# controls_rev_2.net
KiCad netlist of a schematic drawn in EAGLE
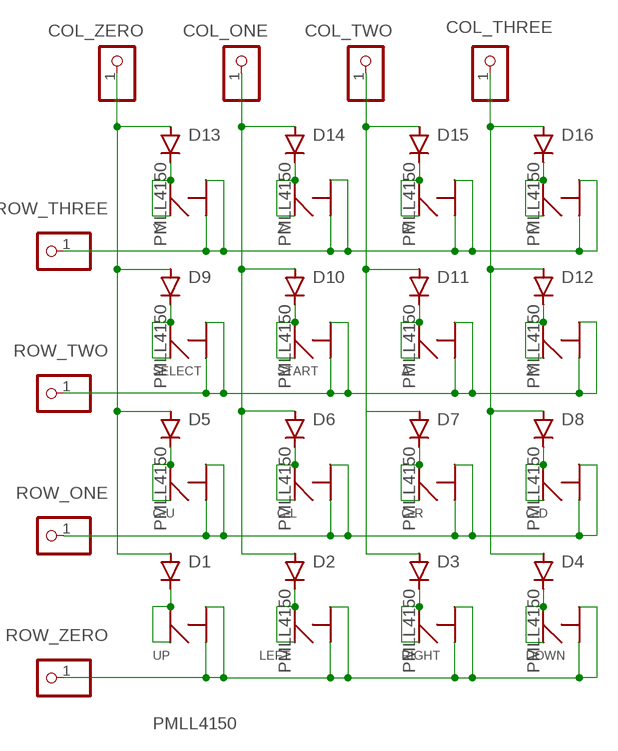
[diagram p0: schematic, sheet 1]

(export (version "E")
  (design (tool "Eeschema 10.0.6"))
  (components
    (comp (ref "A")
      (value "EVQQ2")
      (footprint "eagle-import:TACT")
      (libsource (lib "eagle-import") (part "EVQQ2"))
    )
    (comp (ref "B")
      (value "EVQQ2")
      (footprint "eagle-import:TACT")
      (libsource (lib "eagle-import") (part "EVQQ2"))
    )
    (comp (ref "C")
      (value "EVQQ2")
      (footprint "eagle-import:TACT")
      (libsource (lib "eagle-import") (part "EVQQ2"))
    )
    (comp (ref "C-D")
      (value "EVQQ2")
      (footprint "eagle-import:TACT")
      (libsource (lib "eagle-import") (part "EVQQ2"))
    )
    (comp (ref "C-L")
      (value "EVQQ2")
      (footprint "eagle-import:TACT")
      (libsource (lib "eagle-import") (part "EVQQ2"))
    )
    (comp (ref "C-R")
      (value "EVQQ2")
      (footprint "eagle-import:TACT")
      (libsource (lib "eagle-import") (part "EVQQ2"))
    )
    (comp (ref "C-U")
      (value "EVQQ2")
      (footprint "eagle-import:TACT")
      (libsource (lib "eagle-import") (part "EVQQ2"))
    )
    (comp (ref "COL_ONE")
      (value "PINHD-1X1")
      (footprint "eagle-import:1X01")
      (libsource (lib "eagle-import") (part "PINHD-1X1"))
    )
    (comp (ref "COL_THREE")
      (value "PINHD-1X1")
      (footprint "eagle-import:1X01")
      (libsource (lib "eagle-import") (part "PINHD-1X1"))
    )
    (comp (ref "COL_TWO")
      (value "PINHD-1X1")
      (footprint "eagle-import:1X01")
      (libsource (lib "eagle-import") (part "PINHD-1X1"))
    )
    (comp (ref "COL_ZERO")
      (value "PINHD-1X1")
      (footprint "eagle-import:1X01")
      (libsource (lib "eagle-import") (part "PINHD-1X1"))
    )
    (comp (ref "D1")
      (value "PMLL4150")
      (footprint "eagle-import:SOD80C")
      (libsource (lib "eagle-import") (part "PMLL4150"))
    )
    (comp (ref "D2")
      (value "PMLL4150")
      (footprint "eagle-import:SOD80C")
      (libsource (lib "eagle-import") (part "PMLL4150"))
    )
    (comp (ref "D3")
      (value "PMLL4150")
      (footprint "eagle-import:SOD80C")
      (libsource (lib "eagle-import") (part "PMLL4150"))
    )
    (comp (ref "D4")
      (value "PMLL4150")
      (footprint "eagle-import:SOD80C")
      (libsource (lib "eagle-import") (part "PMLL4150"))
    )
    (comp (ref "D5")
      (value "PMLL4150")
      (footprint "eagle-import:SOD80C")
      (libsource (lib "eagle-import") (part "PMLL4150"))
    )
    (comp (ref "D6")
      (value "PMLL4150")
      (footprint "eagle-import:SOD80C")
      (libsource (lib "eagle-import") (part "PMLL4150"))
    )
    (comp (ref "D7")
      (value "PMLL4150")
      (footprint "eagle-import:SOD80C")
      (libsource (lib "eagle-import") (part "PMLL4150"))
    )
    (comp (ref "D8")
      (value "PMLL4150")
      (footprint "eagle-import:SOD80C")
      (libsource (lib "eagle-import") (part "PMLL4150"))
    )
    (comp (ref "D9")
      (value "PMLL4150")
      (footprint "eagle-import:SOD80C")
      (libsource (lib "eagle-import") (part "PMLL4150"))
    )
    (comp (ref "D10")
      (value "PMLL4150")
      (footprint "eagle-import:SOD80C")
      (libsource (lib "eagle-import") (part "PMLL4150"))
    )
    (comp (ref "D11")
      (value "PMLL4150")
      (footprint "eagle-import:SOD80C")
      (libsource (lib "eagle-import") (part "PMLL4150"))
    )
    (comp (ref "D12")
      (value "PMLL4150")
      (footprint "eagle-import:SOD80C")
      (libsource (lib "eagle-import") (part "PMLL4150"))
    )
    (comp (ref "D13")
      (value "PMLL4150")
      (footprint "eagle-import:SOD80C")
      (libsource (lib "eagle-import") (part "PMLL4150"))
    )
    (comp (ref "D14")
      (value "PMLL4150")
      (footprint "eagle-import:SOD80C")
      (libsource (lib "eagle-import") (part "PMLL4150"))
    )
    (comp (ref "D15")
      (value "PMLL4150")
      (footprint "eagle-import:SOD80C")
      (libsource (lib "eagle-import") (part "PMLL4150"))
    )
    (comp (ref "D16")
      (value "PMLL4150")
      (footprint "eagle-import:SOD80C")
      (libsource (lib "eagle-import") (part "PMLL4150"))
    )
    (comp (ref "DOWN")
      (value "EVQQ2")
      (footprint "eagle-import:TACT")
      (libsource (lib "eagle-import") (part "EVQQ2"))
    )
    (comp (ref "LEFT")
      (value "EVQQ2")
      (footprint "eagle-import:TACT")
      (libsource (lib "eagle-import") (part "EVQQ2"))
    )
    (comp (ref "RIGHT")
      (value "EVQQ2")
      (footprint "eagle-import:TACT")
      (libsource (lib "eagle-import") (part "EVQQ2"))
    )
    (comp (ref "ROW_ONE")
      (value "PINHD-1X1")
      (footprint "eagle-import:1X01")
      (libsource (lib "eagle-import") (part "PINHD-1X1"))
    )
    (comp (ref "ROW_THREE")
      (value "PINHD-1X1")
      (footprint "eagle-import:1X01")
      (libsource (lib "eagle-import") (part "PINHD-1X1"))
    )
    (comp (ref "ROW_TWO")
      (value "PINHD-1X1")
      (footprint "eagle-import:1X01")
      (libsource (lib "eagle-import") (part "PINHD-1X1"))
    )
    (comp (ref "ROW_ZERO")
      (value "PINHD-1X1")
      (footprint "eagle-import:1X01")
      (libsource (lib "eagle-import") (part "PINHD-1X1"))
    )
    (comp (ref "SELECT")
      (value "EVQQ2")
      (footprint "eagle-import:TACT")
      (libsource (lib "eagle-import") (part "EVQQ2"))
    )
    (comp (ref "START")
      (value "EVQQ2")
      (footprint "eagle-import:TACT")
      (libsource (lib "eagle-import") (part "EVQQ2"))
    )
    (comp (ref "UP")
      (value "EVQQ2")
      (footprint "eagle-import:TACT")
      (libsource (lib "eagle-import") (part "EVQQ2"))
    )
    (comp (ref "X")
      (value "EVQQ2")
      (footprint "eagle-import:TACT")
      (libsource (lib "eagle-import") (part "EVQQ2"))
    )
    (comp (ref "Y")
      (value "EVQQ2")
      (footprint "eagle-import:TACT")
      (libsource (lib "eagle-import") (part "EVQQ2"))
    )
    (comp (ref "Z")
      (value "EVQQ2")
      (footprint "eagle-import:TACT")
      (libsource (lib "eagle-import") (part "EVQQ2"))
    )
  )
  (nets
    (net (code "1") (name "Net-(A-PadP$1)") (class "Default")
      (node (ref "A") (pin "P$1") (pinfunction "P$1_P$1") (pintype "bidirectional"))
      (node (ref "A") (pin "P$4") (pinfunction "P$4_P$4") (pintype "bidirectional"))
      (node (ref "D11") (pin "C") (pinfunction "C_C") (pintype "passive"))
    )
    (net (code "2") (name "Net-(A-PadP$2)") (class "Default")
      (node (ref "A") (pin "P$2") (pinfunction "P$2_P$2") (pintype "bidirectional"))
      (node (ref "A") (pin "P$3") (pinfunction "P$3_P$3") (pintype "bidirectional"))
      (node (ref "ROW_TWO") (pin "1") (pinfunction "1_1") (pintype "passive"))
      (node (ref "SELECT") (pin "P$2") (pinfunction "P$2_P$2") (pintype "bidirectional"))
      (node (ref "SELECT") (pin "P$3") (pinfunction "P$3_P$3") (pintype "bidirectional"))
      (node (ref "START") (pin "P$2") (pinfunction "P$2_P$2") (pintype "bidirectional"))
      (node (ref "START") (pin "P$3") (pinfunction "P$3_P$3") (pintype "bidirectional"))
      (node (ref "X") (pin "P$2") (pinfunction "P$2_P$2") (pintype "bidirectional"))
      (node (ref "X") (pin "P$3") (pinfunction "P$3_P$3") (pintype "bidirectional"))
    )
    (net (code "3") (name "Net-(B-PadP$1)") (class "Default")
      (node (ref "B") (pin "P$1") (pinfunction "P$1_P$1") (pintype "bidirectional"))
      (node (ref "B") (pin "P$4") (pinfunction "P$4_P$4") (pintype "bidirectional"))
      (node (ref "D15") (pin "C") (pinfunction "C_C") (pintype "passive"))
    )
    (net (code "4") (name "Net-(B-PadP$2)") (class "Default")
      (node (ref "B") (pin "P$2") (pinfunction "P$2_P$2") (pintype "bidirectional"))
      (node (ref "B") (pin "P$3") (pinfunction "P$3_P$3") (pintype "bidirectional"))
      (node (ref "C") (pin "P$2") (pinfunction "P$2_P$2") (pintype "bidirectional"))
      (node (ref "C") (pin "P$3") (pinfunction "P$3_P$3") (pintype "bidirectional"))
      (node (ref "ROW_THREE") (pin "1") (pinfunction "1_1") (pintype "passive"))
      (node (ref "Y") (pin "P$2") (pinfunction "P$2_P$2") (pintype "bidirectional"))
      (node (ref "Y") (pin "P$3") (pinfunction "P$3_P$3") (pintype "bidirectional"))
      (node (ref "Z") (pin "P$2") (pinfunction "P$2_P$2") (pintype "bidirectional"))
      (node (ref "Z") (pin "P$3") (pinfunction "P$3_P$3") (pintype "bidirectional"))
    )
    (net (code "5") (name "Net-(C-D-PadP$1)") (class "Default")
      (node (ref "C-D") (pin "P$1") (pinfunction "P$1_P$1") (pintype "bidirectional"))
      (node (ref "C-D") (pin "P$4") (pinfunction "P$4_P$4") (pintype "bidirectional"))
      (node (ref "D8") (pin "C") (pinfunction "C_C") (pintype "passive"))
    )
    (net (code "6") (name "Net-(C-D-PadP$2)") (class "Default")
      (node (ref "C-D") (pin "P$2") (pinfunction "P$2_P$2") (pintype "bidirectional"))
      (node (ref "C-D") (pin "P$3") (pinfunction "P$3_P$3") (pintype "bidirectional"))
      (node (ref "C-L") (pin "P$2") (pinfunction "P$2_P$2") (pintype "bidirectional"))
      (node (ref "C-L") (pin "P$3") (pinfunction "P$3_P$3") (pintype "bidirectional"))
      (node (ref "C-R") (pin "P$2") (pinfunction "P$2_P$2") (pintype "bidirectional"))
      (node (ref "C-R") (pin "P$3") (pinfunction "P$3_P$3") (pintype "bidirectional"))
      (node (ref "C-U") (pin "P$2") (pinfunction "P$2_P$2") (pintype "bidirectional"))
      (node (ref "C-U") (pin "P$3") (pinfunction "P$3_P$3") (pintype "bidirectional"))
      (node (ref "ROW_ONE") (pin "1") (pinfunction "1_1") (pintype "passive"))
    )
    (net (code "7") (name "Net-(C-L-PadP$1)") (class "Default")
      (node (ref "C-L") (pin "P$1") (pinfunction "P$1_P$1") (pintype "bidirectional"))
      (node (ref "C-L") (pin "P$4") (pinfunction "P$4_P$4") (pintype "bidirectional"))
      (node (ref "D6") (pin "C") (pinfunction "C_C") (pintype "passive"))
    )
    (net (code "8") (name "Net-(C-PadP$1)") (class "Default")
      (node (ref "C") (pin "P$1") (pinfunction "P$1_P$1") (pintype "bidirectional"))
      (node (ref "C") (pin "P$4") (pinfunction "P$4_P$4") (pintype "bidirectional"))
      (node (ref "D16") (pin "C") (pinfunction "C_C") (pintype "passive"))
    )
    (net (code "9") (name "Net-(C-R-PadP$1)") (class "Default")
      (node (ref "C-R") (pin "P$1") (pinfunction "P$1_P$1") (pintype "bidirectional"))
      (node (ref "C-R") (pin "P$4") (pinfunction "P$4_P$4") (pintype "bidirectional"))
      (node (ref "D7") (pin "C") (pinfunction "C_C") (pintype "passive"))
    )
    (net (code "10") (name "Net-(C-U-PadP$1)") (class "Default")
      (node (ref "C-U") (pin "P$1") (pinfunction "P$1_P$1") (pintype "bidirectional"))
      (node (ref "C-U") (pin "P$4") (pinfunction "P$4_P$4") (pintype "bidirectional"))
      (node (ref "D5") (pin "C") (pinfunction "C_C") (pintype "passive"))
    )
    (net (code "11") (name "Net-(COL_ONE-Pad1)") (class "Default")
      (node (ref "COL_ONE") (pin "1") (pinfunction "1_1") (pintype "passive"))
      (node (ref "D10") (pin "A") (pinfunction "A_A") (pintype "passive"))
      (node (ref "D14") (pin "A") (pinfunction "A_A") (pintype "passive"))
      (node (ref "D2") (pin "A") (pinfunction "A_A") (pintype "passive"))
      (node (ref "D6") (pin "A") (pinfunction "A_A") (pintype "passive"))
    )
    (net (code "12") (name "Net-(COL_THREE-Pad1)") (class "Default")
      (node (ref "COL_THREE") (pin "1") (pinfunction "1_1") (pintype "passive"))
      (node (ref "D12") (pin "A") (pinfunction "A_A") (pintype "passive"))
      (node (ref "D16") (pin "A") (pinfunction "A_A") (pintype "passive"))
      (node (ref "D4") (pin "A") (pinfunction "A_A") (pintype "passive"))
      (node (ref "D8") (pin "A") (pinfunction "A_A") (pintype "passive"))
    )
    (net (code "13") (name "Net-(COL_TWO-Pad1)") (class "Default")
      (node (ref "COL_TWO") (pin "1") (pinfunction "1_1") (pintype "passive"))
      (node (ref "D11") (pin "A") (pinfunction "A_A") (pintype "passive"))
      (node (ref "D15") (pin "A") (pinfunction "A_A") (pintype "passive"))
      (node (ref "D3") (pin "A") (pinfunction "A_A") (pintype "passive"))
      (node (ref "D7") (pin "A") (pinfunction "A_A") (pintype "passive"))
    )
    (net (code "14") (name "Net-(COL_ZERO-Pad1)") (class "Default")
      (node (ref "COL_ZERO") (pin "1") (pinfunction "1_1") (pintype "passive"))
      (node (ref "D1") (pin "A") (pinfunction "A_A") (pintype "passive"))
      (node (ref "D13") (pin "A") (pinfunction "A_A") (pintype "passive"))
      (node (ref "D5") (pin "A") (pinfunction "A_A") (pintype "passive"))
      (node (ref "D9") (pin "A") (pinfunction "A_A") (pintype "passive"))
    )
    (net (code "15") (name "Net-(D1-PadC)") (class "Default")
      (node (ref "D1") (pin "C") (pinfunction "C_C") (pintype "passive"))
      (node (ref "UP") (pin "P$1") (pinfunction "P$1_P$1") (pintype "bidirectional"))
      (node (ref "UP") (pin "P$4") (pinfunction "P$4_P$4") (pintype "bidirectional"))
    )
    (net (code "16") (name "Net-(D2-PadC)") (class "Default")
      (node (ref "D2") (pin "C") (pinfunction "C_C") (pintype "passive"))
      (node (ref "LEFT") (pin "P$1") (pinfunction "P$1_P$1") (pintype "bidirectional"))
      (node (ref "LEFT") (pin "P$4") (pinfunction "P$4_P$4") (pintype "bidirectional"))
    )
    (net (code "17") (name "Net-(D3-PadC)") (class "Default")
      (node (ref "D3") (pin "C") (pinfunction "C_C") (pintype "passive"))
      (node (ref "RIGHT") (pin "P$1") (pinfunction "P$1_P$1") (pintype "bidirectional"))
      (node (ref "RIGHT") (pin "P$4") (pinfunction "P$4_P$4") (pintype "bidirectional"))
    )
    (net (code "18") (name "Net-(D4-PadC)") (class "Default")
      (node (ref "D4") (pin "C") (pinfunction "C_C") (pintype "passive"))
      (node (ref "DOWN") (pin "P$1") (pinfunction "P$1_P$1") (pintype "bidirectional"))
      (node (ref "DOWN") (pin "P$4") (pinfunction "P$4_P$4") (pintype "bidirectional"))
    )
    (net (code "19") (name "Net-(D9-PadC)") (class "Default")
      (node (ref "D9") (pin "C") (pinfunction "C_C") (pintype "passive"))
      (node (ref "SELECT") (pin "P$1") (pinfunction "P$1_P$1") (pintype "bidirectional"))
      (node (ref "SELECT") (pin "P$4") (pinfunction "P$4_P$4") (pintype "bidirectional"))
    )
    (net (code "20") (name "Net-(D10-PadC)") (class "Default")
      (node (ref "D10") (pin "C") (pinfunction "C_C") (pintype "passive"))
      (node (ref "START") (pin "P$1") (pinfunction "P$1_P$1") (pintype "bidirectional"))
      (node (ref "START") (pin "P$4") (pinfunction "P$4_P$4") (pintype "bidirectional"))
    )
    (net (code "21") (name "Net-(D12-PadC)") (class "Default")
      (node (ref "D12") (pin "C") (pinfunction "C_C") (pintype "passive"))
      (node (ref "X") (pin "P$1") (pinfunction "P$1_P$1") (pintype "bidirectional"))
      (node (ref "X") (pin "P$4") (pinfunction "P$4_P$4") (pintype "bidirectional"))
    )
    (net (code "22") (name "Net-(D13-PadC)") (class "Default")
      (node (ref "D13") (pin "C") (pinfunction "C_C") (pintype "passive"))
      (node (ref "Y") (pin "P$1") (pinfunction "P$1_P$1") (pintype "bidirectional"))
      (node (ref "Y") (pin "P$4") (pinfunction "P$4_P$4") (pintype "bidirectional"))
    )
    (net (code "23") (name "Net-(D14-PadC)") (class "Default")
      (node (ref "D14") (pin "C") (pinfunction "C_C") (pintype "passive"))
      (node (ref "Z") (pin "P$1") (pinfunction "P$1_P$1") (pintype "bidirectional"))
      (node (ref "Z") (pin "P$4") (pinfunction "P$4_P$4") (pintype "bidirectional"))
    )
    (net (code "24") (name "Net-(DOWN-PadP$2)") (class "Default")
      (node (ref "DOWN") (pin "P$2") (pinfunction "P$2_P$2") (pintype "bidirectional"))
      (node (ref "DOWN") (pin "P$3") (pinfunction "P$3_P$3") (pintype "bidirectional"))
      (node (ref "LEFT") (pin "P$2") (pinfunction "P$2_P$2") (pintype "bidirectional"))
      (node (ref "LEFT") (pin "P$3") (pinfunction "P$3_P$3") (pintype "bidirectional"))
      (node (ref "RIGHT") (pin "P$2") (pinfunction "P$2_P$2") (pintype "bidirectional"))
      (node (ref "RIGHT") (pin "P$3") (pinfunction "P$3_P$3") (pintype "bidirectional"))
      (node (ref "ROW_ZERO") (pin "1") (pinfunction "1_1") (pintype "passive"))
      (node (ref "UP") (pin "P$2") (pinfunction "P$2_P$2") (pintype "bidirectional"))
      (node (ref "UP") (pin "P$3") (pinfunction "P$3_P$3") (pintype "bidirectional"))
    )
  )
)
